# Thermistor_ADC.net
KiCad netlist of a schematic drawn in Altium Designer
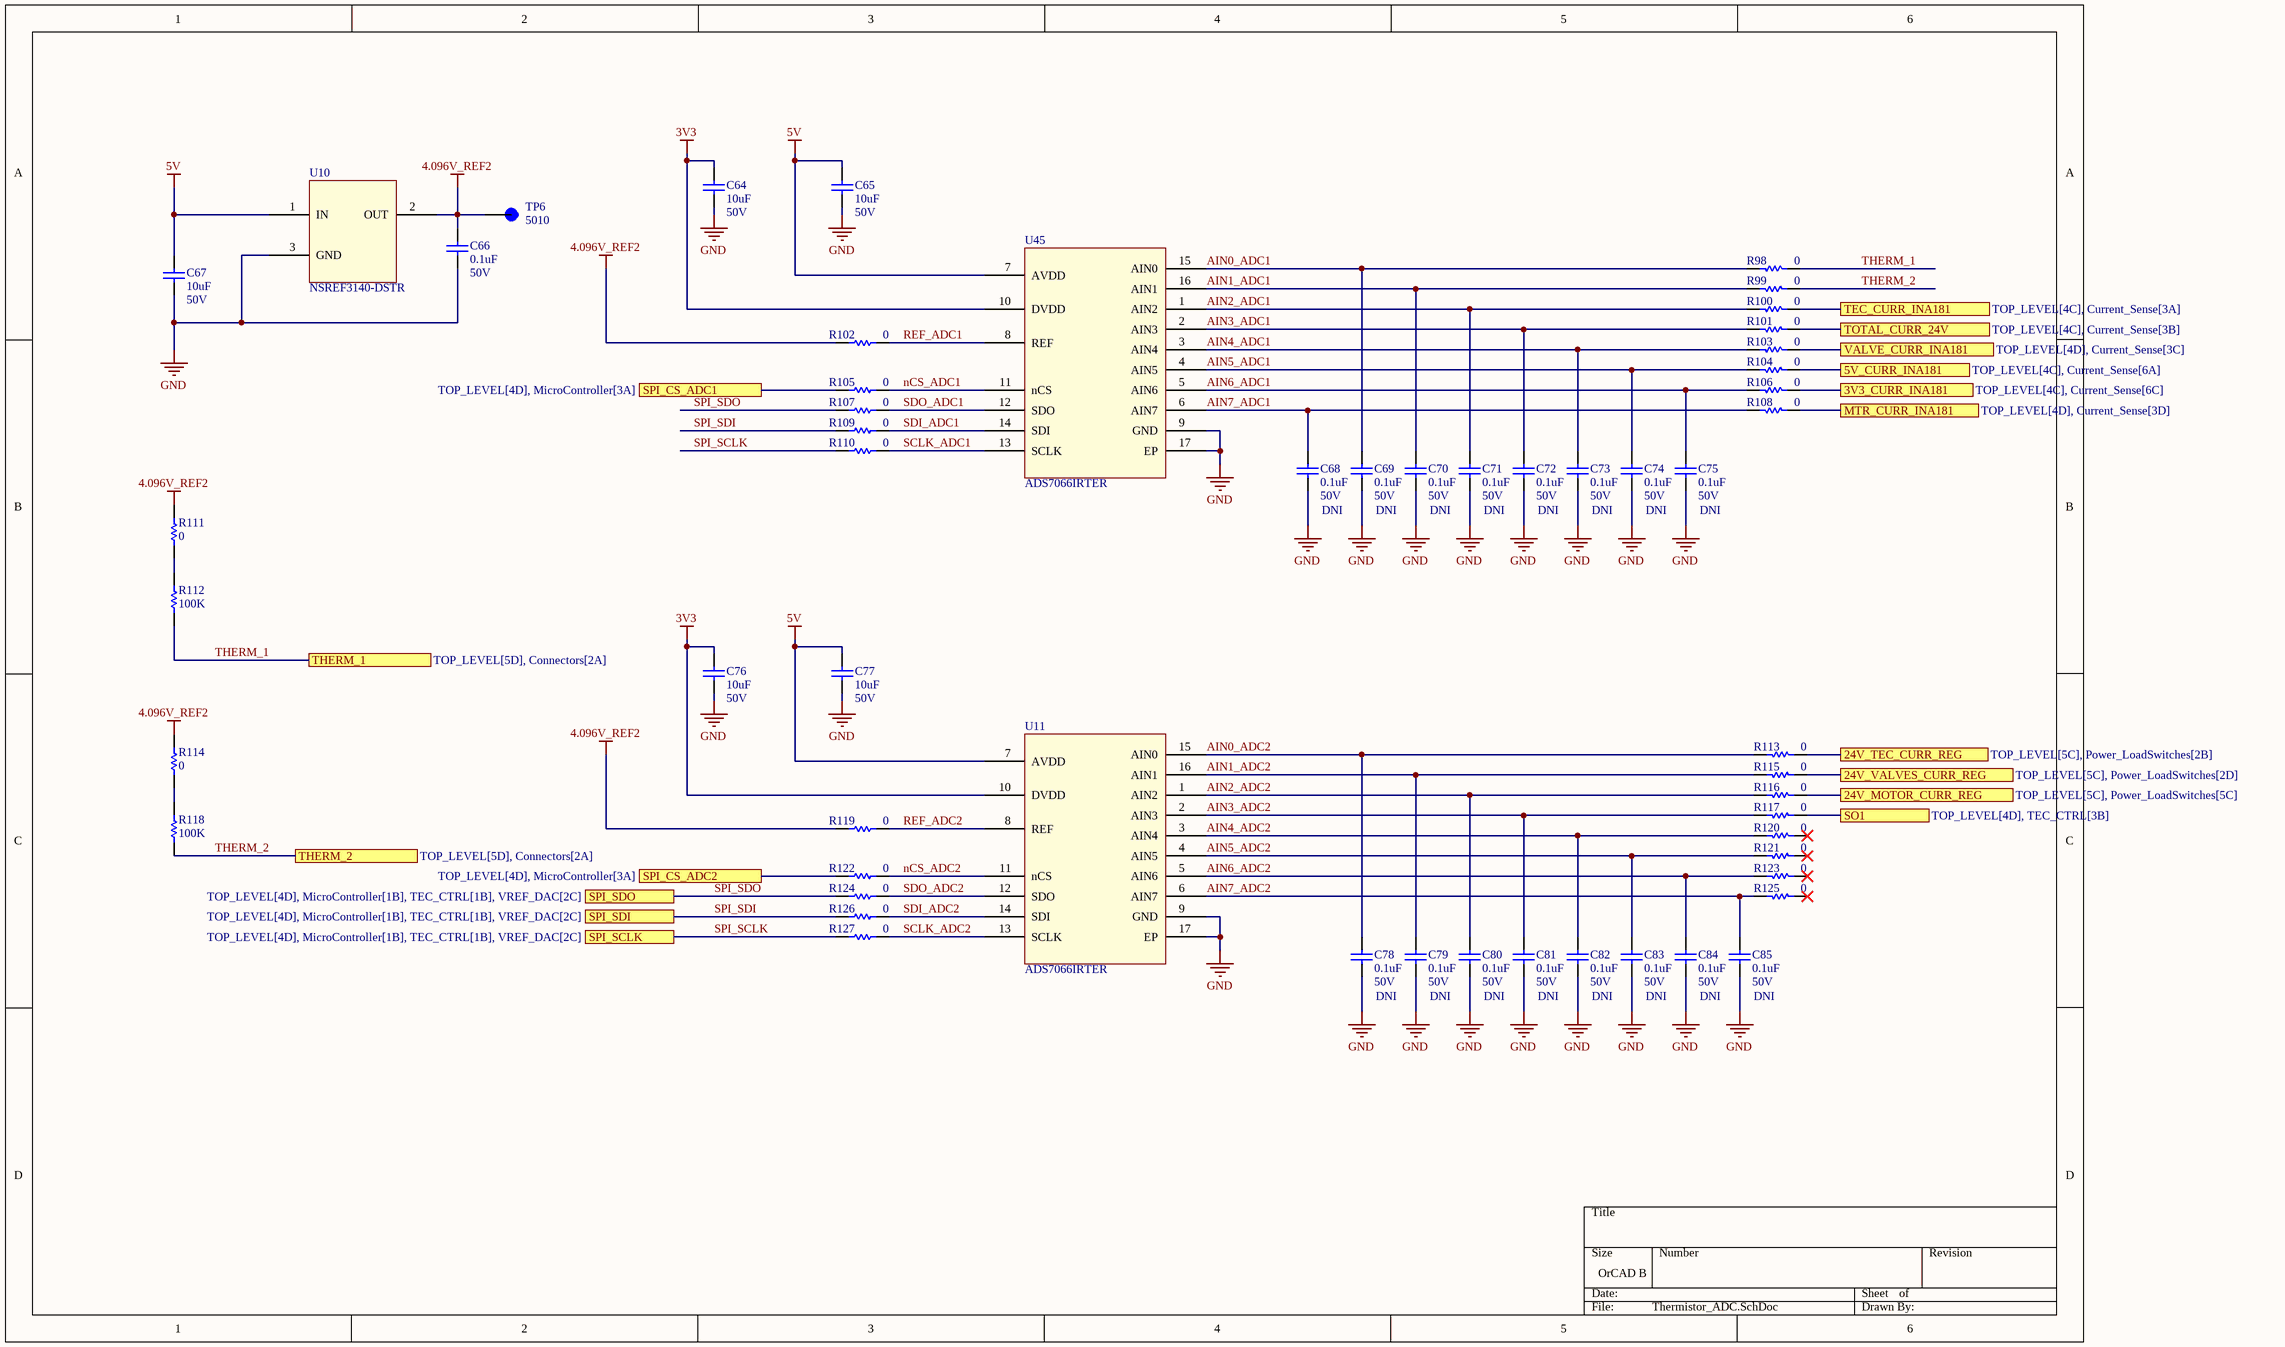
[diagram p0: Thermistor_ADC.SchDoc]

(export (version "E")
  (design (tool "Eeschema 10.0.6"))
  (components
    (comp (ref "C64")
      (value "10uF")
      (footprint "DEFAULT_CAPACITOR_0805")
      (description "CAP CER 10UF 50V X5R 0805")
      (fields (field (name "RATING") "50V") (field (name "Comment") "GRM21BR61H106KE43L"))
      (libsource (lib "Avery Altium Llibrary") (part "GRM21BR61H106KE43L"))
    )
    (comp (ref "C65")
      (value "10uF")
      (footprint "DEFAULT_CAPACITOR_0805")
      (description "CAP CER 10UF 50V X5R 0805")
      (fields (field (name "RATING") "50V") (field (name "Comment") "GRM21BR61H106KE43L"))
      (libsource (lib "Avery Altium Llibrary") (part "GRM21BR61H106KE43L"))
    )
    (comp (ref "C66")
      (value "0.1uF")
      (footprint "DEFAULT_CAPACITOR_0805")
      (description "CAP CER 0.1UF 50V X7R 0805")
      (fields
        (field (name "MANUFACTURER") "Cal-Chip Electronics, Inc.")
        (field (name "RATING") "50V")
        (field (name "Comment") "KGM21NR71H104KT")
      )
      (libsource (lib "Avery Altium Llibrary") (part "KGM21NR71H104KT"))
    )
    (comp (ref "C67")
      (value "10uF")
      (footprint "DEFAULT_CAPACITOR_0805")
      (description "CAP CER 10UF 50V X5R 0805")
      (fields (field (name "RATING") "50V") (field (name "Comment") "GRM21BR61H106KE43L"))
      (libsource (lib "Avery Altium Llibrary") (part "GRM21BR61H106KE43L"))
    )
    (comp (ref "C68")
      (value "DNI")
      (footprint "DEFAULT_CAPACITOR_0805")
      (description "CAP CER 0.1UF 50V X7R 0805")
      (fields
        (field (name "MANUFACTURER") "Cal-Chip Electronics, Inc.")
        (field (name "RATING") "50V")
        (field (name "ALTIUM_VALUE") "0.1uF")
      )
      (libsource (lib "Avery Altium Llibrary") (part "KGM21NR71H104KT"))
    )
    (comp (ref "C69")
      (value "DNI")
      (footprint "DEFAULT_CAPACITOR_0805")
      (description "CAP CER 0.1UF 50V X7R 0805")
      (fields
        (field (name "MANUFACTURER") "Cal-Chip Electronics, Inc.")
        (field (name "RATING") "50V")
        (field (name "ALTIUM_VALUE") "0.1uF")
      )
      (libsource (lib "Avery Altium Llibrary") (part "KGM21NR71H104KT"))
    )
    (comp (ref "C70")
      (value "DNI")
      (footprint "DEFAULT_CAPACITOR_0805")
      (description "CAP CER 0.1UF 50V X7R 0805")
      (fields
        (field (name "MANUFACTURER") "Cal-Chip Electronics, Inc.")
        (field (name "RATING") "50V")
        (field (name "ALTIUM_VALUE") "0.1uF")
      )
      (libsource (lib "Avery Altium Llibrary") (part "KGM21NR71H104KT"))
    )
    (comp (ref "C71")
      (value "DNI")
      (footprint "DEFAULT_CAPACITOR_0805")
      (description "CAP CER 0.1UF 50V X7R 0805")
      (fields
        (field (name "MANUFACTURER") "Cal-Chip Electronics, Inc.")
        (field (name "RATING") "50V")
        (field (name "ALTIUM_VALUE") "0.1uF")
      )
      (libsource (lib "Avery Altium Llibrary") (part "KGM21NR71H104KT"))
    )
    (comp (ref "C72")
      (value "DNI")
      (footprint "DEFAULT_CAPACITOR_0805")
      (description "CAP CER 0.1UF 50V X7R 0805")
      (fields
        (field (name "MANUFACTURER") "Cal-Chip Electronics, Inc.")
        (field (name "RATING") "50V")
        (field (name "ALTIUM_VALUE") "0.1uF")
      )
      (libsource (lib "Avery Altium Llibrary") (part "KGM21NR71H104KT"))
    )
    (comp (ref "C73")
      (value "DNI")
      (footprint "DEFAULT_CAPACITOR_0805")
      (description "CAP CER 0.1UF 50V X7R 0805")
      (fields
        (field (name "MANUFACTURER") "Cal-Chip Electronics, Inc.")
        (field (name "RATING") "50V")
        (field (name "ALTIUM_VALUE") "0.1uF")
      )
      (libsource (lib "Avery Altium Llibrary") (part "KGM21NR71H104KT"))
    )
    (comp (ref "C74")
      (value "DNI")
      (footprint "DEFAULT_CAPACITOR_0805")
      (description "CAP CER 0.1UF 50V X7R 0805")
      (fields
        (field (name "MANUFACTURER") "Cal-Chip Electronics, Inc.")
        (field (name "RATING") "50V")
        (field (name "ALTIUM_VALUE") "0.1uF")
      )
      (libsource (lib "Avery Altium Llibrary") (part "KGM21NR71H104KT"))
    )
    (comp (ref "C75")
      (value "DNI")
      (footprint "DEFAULT_CAPACITOR_0805")
      (description "CAP CER 0.1UF 50V X7R 0805")
      (fields
        (field (name "MANUFACTURER") "Cal-Chip Electronics, Inc.")
        (field (name "RATING") "50V")
        (field (name "ALTIUM_VALUE") "0.1uF")
      )
      (libsource (lib "Avery Altium Llibrary") (part "KGM21NR71H104KT"))
    )
    (comp (ref "C76")
      (value "10uF")
      (footprint "DEFAULT_CAPACITOR_0805")
      (description "CAP CER 10UF 50V X5R 0805")
      (fields (field (name "RATING") "50V") (field (name "Comment") "GRM21BR61H106KE43L"))
      (libsource (lib "Avery Altium Llibrary") (part "GRM21BR61H106KE43L"))
    )
    (comp (ref "C77")
      (value "10uF")
      (footprint "DEFAULT_CAPACITOR_0805")
      (description "CAP CER 10UF 50V X5R 0805")
      (fields (field (name "RATING") "50V") (field (name "Comment") "GRM21BR61H106KE43L"))
      (libsource (lib "Avery Altium Llibrary") (part "GRM21BR61H106KE43L"))
    )
    (comp (ref "C78")
      (value "DNI")
      (footprint "DEFAULT_CAPACITOR_0805")
      (description "CAP CER 0.1UF 50V X7R 0805")
      (fields
        (field (name "MANUFACTURER") "Cal-Chip Electronics, Inc.")
        (field (name "RATING") "50V")
        (field (name "ALTIUM_VALUE") "0.1uF")
      )
      (libsource (lib "Avery Altium Llibrary") (part "KGM21NR71H104KT"))
    )
    (comp (ref "C79")
      (value "DNI")
      (footprint "DEFAULT_CAPACITOR_0805")
      (description "CAP CER 0.1UF 50V X7R 0805")
      (fields
        (field (name "MANUFACTURER") "Cal-Chip Electronics, Inc.")
        (field (name "RATING") "50V")
        (field (name "ALTIUM_VALUE") "0.1uF")
      )
      (libsource (lib "Avery Altium Llibrary") (part "KGM21NR71H104KT"))
    )
    (comp (ref "C80")
      (value "DNI")
      (footprint "DEFAULT_CAPACITOR_0805")
      (description "CAP CER 0.1UF 50V X7R 0805")
      (fields
        (field (name "MANUFACTURER") "Cal-Chip Electronics, Inc.")
        (field (name "RATING") "50V")
        (field (name "ALTIUM_VALUE") "0.1uF")
      )
      (libsource (lib "Avery Altium Llibrary") (part "KGM21NR71H104KT"))
    )
    (comp (ref "C81")
      (value "DNI")
      (footprint "DEFAULT_CAPACITOR_0805")
      (description "CAP CER 0.1UF 50V X7R 0805")
      (fields
        (field (name "MANUFACTURER") "Cal-Chip Electronics, Inc.")
        (field (name "RATING") "50V")
        (field (name "ALTIUM_VALUE") "0.1uF")
      )
      (libsource (lib "Avery Altium Llibrary") (part "KGM21NR71H104KT"))
    )
    (comp (ref "C82")
      (value "DNI")
      (footprint "DEFAULT_CAPACITOR_0805")
      (description "CAP CER 0.1UF 50V X7R 0805")
      (fields
        (field (name "MANUFACTURER") "Cal-Chip Electronics, Inc.")
        (field (name "RATING") "50V")
        (field (name "ALTIUM_VALUE") "0.1uF")
      )
      (libsource (lib "Avery Altium Llibrary") (part "KGM21NR71H104KT"))
    )
    (comp (ref "C83")
      (value "DNI")
      (footprint "DEFAULT_CAPACITOR_0805")
      (description "CAP CER 0.1UF 50V X7R 0805")
      (fields
        (field (name "MANUFACTURER") "Cal-Chip Electronics, Inc.")
        (field (name "RATING") "50V")
        (field (name "ALTIUM_VALUE") "0.1uF")
      )
      (libsource (lib "Avery Altium Llibrary") (part "KGM21NR71H104KT"))
    )
    (comp (ref "C84")
      (value "DNI")
      (footprint "DEFAULT_CAPACITOR_0805")
      (description "CAP CER 0.1UF 50V X7R 0805")
      (fields
        (field (name "MANUFACTURER") "Cal-Chip Electronics, Inc.")
        (field (name "RATING") "50V")
        (field (name "ALTIUM_VALUE") "0.1uF")
      )
      (libsource (lib "Avery Altium Llibrary") (part "KGM21NR71H104KT"))
    )
    (comp (ref "C85")
      (value "DNI")
      (footprint "DEFAULT_CAPACITOR_0805")
      (description "CAP CER 0.1UF 50V X7R 0805")
      (fields
        (field (name "MANUFACTURER") "Cal-Chip Electronics, Inc.")
        (field (name "RATING") "50V")
        (field (name "ALTIUM_VALUE") "0.1uF")
      )
      (libsource (lib "Avery Altium Llibrary") (part "KGM21NR71H104KT"))
    )
    (comp (ref "R98")
      (value "0")
      (footprint "DEFAULT_RESISTOR_0805")
      (description "RES 0 OHM JUMPER 1/8W 0805")
      (fields (field (name "POWER") "1/8W") (field (name "Comment") "RC0805JR-070RL"))
      (libsource (lib "Avery Altium Llibrary") (part "RC0805JR-070RL"))
    )
    (comp (ref "R99")
      (value "0")
      (footprint "DEFAULT_RESISTOR_0805")
      (description "RES 0 OHM JUMPER 1/8W 0805")
      (fields (field (name "POWER") "1/8W") (field (name "Comment") "RC0805JR-070RL"))
      (libsource (lib "Avery Altium Llibrary") (part "RC0805JR-070RL"))
    )
    (comp (ref "R100")
      (value "0")
      (footprint "DEFAULT_RESISTOR_0805")
      (description "RES 0 OHM JUMPER 1/8W 0805")
      (fields (field (name "POWER") "1/8W") (field (name "Comment") "RC0805JR-070RL"))
      (libsource (lib "Avery Altium Llibrary") (part "RC0805JR-070RL"))
    )
    (comp (ref "R101")
      (value "0")
      (footprint "DEFAULT_RESISTOR_0805")
      (description "RES 0 OHM JUMPER 1/8W 0805")
      (fields (field (name "POWER") "1/8W") (field (name "Comment") "RC0805JR-070RL"))
      (libsource (lib "Avery Altium Llibrary") (part "RC0805JR-070RL"))
    )
    (comp (ref "R102")
      (value "0")
      (footprint "DEFAULT_RESISTOR_0805")
      (description "RES 0 OHM JUMPER 1/8W 0805")
      (fields (field (name "POWER") "1/8W") (field (name "Comment") "RC0805JR-070RL"))
      (libsource (lib "Avery Altium Llibrary") (part "RC0805JR-070RL"))
    )
    (comp (ref "R103")
      (value "0")
      (footprint "DEFAULT_RESISTOR_0805")
      (description "RES 0 OHM JUMPER 1/8W 0805")
      (fields (field (name "POWER") "1/8W") (field (name "Comment") "RC0805JR-070RL"))
      (libsource (lib "Avery Altium Llibrary") (part "RC0805JR-070RL"))
    )
    (comp (ref "R104")
      (value "0")
      (footprint "DEFAULT_RESISTOR_0805")
      (description "RES 0 OHM JUMPER 1/8W 0805")
      (fields (field (name "POWER") "1/8W") (field (name "Comment") "RC0805JR-070RL"))
      (libsource (lib "Avery Altium Llibrary") (part "RC0805JR-070RL"))
    )
    (comp (ref "R105")
      (value "0")
      (footprint "DEFAULT_RESISTOR_0805")
      (description "RES 0 OHM JUMPER 1/8W 0805")
      (fields (field (name "POWER") "1/8W") (field (name "Comment") "RC0805JR-070RL"))
      (libsource (lib "Avery Altium Llibrary") (part "RC0805JR-070RL"))
    )
    (comp (ref "R106")
      (value "0")
      (footprint "DEFAULT_RESISTOR_0805")
      (description "RES 0 OHM JUMPER 1/8W 0805")
      (fields (field (name "POWER") "1/8W") (field (name "Comment") "RC0805JR-070RL"))
      (libsource (lib "Avery Altium Llibrary") (part "RC0805JR-070RL"))
    )
    (comp (ref "R107")
      (value "0")
      (footprint "DEFAULT_RESISTOR_0805")
      (description "RES 0 OHM JUMPER 1/8W 0805")
      (fields (field (name "POWER") "1/8W") (field (name "Comment") "RC0805JR-070RL"))
      (libsource (lib "Avery Altium Llibrary") (part "RC0805JR-070RL"))
    )
    (comp (ref "R108")
      (value "0")
      (footprint "DEFAULT_RESISTOR_0805")
      (description "RES 0 OHM JUMPER 1/8W 0805")
      (fields (field (name "POWER") "1/8W") (field (name "Comment") "RC0805JR-070RL"))
      (libsource (lib "Avery Altium Llibrary") (part "RC0805JR-070RL"))
    )
    (comp (ref "R109")
      (value "0")
      (footprint "DEFAULT_RESISTOR_0805")
      (description "RES 0 OHM JUMPER 1/8W 0805")
      (fields (field (name "POWER") "1/8W") (field (name "Comment") "RC0805JR-070RL"))
      (libsource (lib "Avery Altium Llibrary") (part "RC0805JR-070RL"))
    )
    (comp (ref "R110")
      (value "0")
      (footprint "DEFAULT_RESISTOR_0805")
      (description "RES 0 OHM JUMPER 1/8W 0805")
      (fields (field (name "POWER") "1/8W") (field (name "Comment") "RC0805JR-070RL"))
      (libsource (lib "Avery Altium Llibrary") (part "RC0805JR-070RL"))
    )
    (comp (ref "R111")
      (value "0")
      (footprint "DEFAULT_RESISTOR_0805")
      (description "RES 0 OHM JUMPER 1/8W 0805")
      (fields (field (name "POWER") "1/8W") (field (name "Comment") "RC0805JR-070RL"))
      (libsource (lib "Avery Altium Llibrary") (part "RC0805JR-070RL"))
    )
    (comp (ref "R112")
      (value "100K")
      (footprint "DEFAULT_RESISTOR_0805")
      (description "RES SMD 100K OHM 0.1% 1/8W 0805")
      (fields (field (name "POWER") "1/8W") (field (name "TOLERANCE") "0.1%"))
      (libsource (lib "Avery Altium Llibrary") (part "RG2012P-104-B-T5"))
    )
    (comp (ref "R113")
      (value "0")
      (footprint "DEFAULT_RESISTOR_0805")
      (description "RES 0 OHM JUMPER 1/8W 0805")
      (fields (field (name "POWER") "1/8W") (field (name "Comment") "RC0805JR-070RL"))
      (libsource (lib "Avery Altium Llibrary") (part "RC0805JR-070RL"))
    )
    (comp (ref "R114")
      (value "0")
      (footprint "DEFAULT_RESISTOR_0805")
      (description "RES 0 OHM JUMPER 1/8W 0805")
      (fields (field (name "POWER") "1/8W") (field (name "Comment") "RC0805JR-070RL"))
      (libsource (lib "Avery Altium Llibrary") (part "RC0805JR-070RL"))
    )
    (comp (ref "R115")
      (value "0")
      (footprint "DEFAULT_RESISTOR_0805")
      (description "RES 0 OHM JUMPER 1/8W 0805")
      (fields (field (name "POWER") "1/8W") (field (name "Comment") "RC0805JR-070RL"))
      (libsource (lib "Avery Altium Llibrary") (part "RC0805JR-070RL"))
    )
    (comp (ref "R116")
      (value "0")
      (footprint "DEFAULT_RESISTOR_0805")
      (description "RES 0 OHM JUMPER 1/8W 0805")
      (fields (field (name "POWER") "1/8W") (field (name "Comment") "RC0805JR-070RL"))
      (libsource (lib "Avery Altium Llibrary") (part "RC0805JR-070RL"))
    )
    (comp (ref "R117")
      (value "0")
      (footprint "DEFAULT_RESISTOR_0805")
      (description "RES 0 OHM JUMPER 1/8W 0805")
      (fields (field (name "POWER") "1/8W") (field (name "Comment") "RC0805JR-070RL"))
      (libsource (lib "Avery Altium Llibrary") (part "RC0805JR-070RL"))
    )
    (comp (ref "R118")
      (value "100K")
      (footprint "DEFAULT_RESISTOR_0805")
      (description "RES SMD 100K OHM 0.1% 1/8W 0805")
      (fields (field (name "POWER") "1/8W") (field (name "TOLERANCE") "0.1%"))
      (libsource (lib "Avery Altium Llibrary") (part "RG2012P-104-B-T5"))
    )
    (comp (ref "R119")
      (value "0")
      (footprint "DEFAULT_RESISTOR_0805")
      (description "RES 0 OHM JUMPER 1/8W 0805")
      (fields (field (name "POWER") "1/8W") (field (name "Comment") "RC0805JR-070RL"))
      (libsource (lib "Avery Altium Llibrary") (part "RC0805JR-070RL"))
    )
    (comp (ref "R120")
      (value "0")
      (footprint "DEFAULT_RESISTOR_0805")
      (description "RES 0 OHM JUMPER 1/8W 0805")
      (fields (field (name "POWER") "1/8W") (field (name "Comment") "RC0805JR-070RL"))
      (libsource (lib "Avery Altium Llibrary") (part "RC0805JR-070RL"))
    )
    (comp (ref "R121")
      (value "0")
      (footprint "DEFAULT_RESISTOR_0805")
      (description "RES 0 OHM JUMPER 1/8W 0805")
      (fields (field (name "POWER") "1/8W") (field (name "Comment") "RC0805JR-070RL"))
      (libsource (lib "Avery Altium Llibrary") (part "RC0805JR-070RL"))
    )
    (comp (ref "R122")
      (value "0")
      (footprint "DEFAULT_RESISTOR_0805")
      (description "RES 0 OHM JUMPER 1/8W 0805")
      (fields (field (name "POWER") "1/8W") (field (name "Comment") "RC0805JR-070RL"))
      (libsource (lib "Avery Altium Llibrary") (part "RC0805JR-070RL"))
    )
    (comp (ref "R123")
      (value "0")
      (footprint "DEFAULT_RESISTOR_0805")
      (description "RES 0 OHM JUMPER 1/8W 0805")
      (fields (field (name "POWER") "1/8W") (field (name "Comment") "RC0805JR-070RL"))
      (libsource (lib "Avery Altium Llibrary") (part "RC0805JR-070RL"))
    )
    (comp (ref "R124")
      (value "0")
      (footprint "DEFAULT_RESISTOR_0805")
      (description "RES 0 OHM JUMPER 1/8W 0805")
      (fields (field (name "POWER") "1/8W") (field (name "Comment") "RC0805JR-070RL"))
      (libsource (lib "Avery Altium Llibrary") (part "RC0805JR-070RL"))
    )
    (comp (ref "R125")
      (value "0")
      (footprint "DEFAULT_RESISTOR_0805")
      (description "RES 0 OHM JUMPER 1/8W 0805")
      (fields (field (name "POWER") "1/8W") (field (name "Comment") "RC0805JR-070RL"))
      (libsource (lib "Avery Altium Llibrary") (part "RC0805JR-070RL"))
    )
    (comp (ref "R126")
      (value "0")
      (footprint "DEFAULT_RESISTOR_0805")
      (description "RES 0 OHM JUMPER 1/8W 0805")
      (fields (field (name "POWER") "1/8W") (field (name "Comment") "RC0805JR-070RL"))
      (libsource (lib "Avery Altium Llibrary") (part "RC0805JR-070RL"))
    )
    (comp (ref "R127")
      (value "0")
      (footprint "DEFAULT_RESISTOR_0805")
      (description "RES 0 OHM JUMPER 1/8W 0805")
      (fields (field (name "POWER") "1/8W") (field (name "Comment") "RC0805JR-070RL"))
      (libsource (lib "Avery Altium Llibrary") (part "RC0805JR-070RL"))
    )
    (comp (ref "TP6")
      (value "5010")
      (footprint "TP_5011")
      (description "PC TEST POINT MULTIPURPOSE RED")
      (libsource (lib "Avery Altium Llibrary") (part "5010"))
    )
    (comp (ref "U10")
      (value "NSREF3140-DSTR")
      (footprint "NSREF3140DSTR-SOT23-3L")
      (description "0.2% ACCURACY 15PPM 4V REF")
      (fields (field (name "MANUFACTURER") "NOVOSENSE"))
      (libsource (lib "Avery Altium Llibrary") (part "NSREF3140-DSTR"))
    )
    (comp (ref "U11")
      (value "ADS7066IRTER")
      (footprint "ADS7066IRTER-WQFN16")
      (description "16 Bit Analog to Digital Converter 8 Input 1 SAR 16-WQFN (3x3)")
      (fields (field (name "MANUFACTURER") "Texas Instruments"))
      (libsource (lib "Avery Schem Library") (part "ADS7066IRTER"))
    )
    (comp (ref "U45")
      (value "ADS7066IRTER")
      (footprint "ADS7066IRTER-WQFN16")
      (description "16 Bit Analog to Digital Converter 8 Input 1 SAR 16-WQFN (3x3)")
      (fields (field (name "MANUFACTURER") "Texas Instruments"))
      (libsource (lib "Avery Schem Library") (part "ADS7066IRTER"))
    )
  )
  (nets
    (net (code "1") (name "/3V3_CURR_INA181") (class "Default")
      (node (ref "R106") (pin "2") (pinfunction "2_2") (pintype "passive"))
    )
    (net (code "2") (name "/5V_CURR_INA181") (class "Default")
      (node (ref "R104") (pin "2") (pinfunction "2_2") (pintype "passive"))
    )
    (net (code "3") (name "/24V_MOTOR_CURR_REG") (class "Default")
      (node (ref "R116") (pin "2") (pinfunction "2_2") (pintype "passive"))
    )
    (net (code "4") (name "/24V_TEC_CURR_REG") (class "Default")
      (node (ref "R113") (pin "2") (pinfunction "2_2") (pintype "passive"))
    )
    (net (code "5") (name "/24V_VALVES_CURR_REG") (class "Default")
      (node (ref "R115") (pin "2") (pinfunction "2_2") (pintype "passive"))
    )
    (net (code "6") (name "/AIN0_ADC1") (class "Default")
      (node (ref "C69") (pin "2") (pinfunction "2_2") (pintype "passive"))
      (node (ref "R98") (pin "1") (pinfunction "1_1") (pintype "passive"))
      (node (ref "U45") (pin "15") (pinfunction "AIN0_15") (pintype "passive"))
    )
    (net (code "7") (name "/AIN0_ADC2") (class "Default")
      (node (ref "C78") (pin "2") (pinfunction "2_2") (pintype "passive"))
      (node (ref "R113") (pin "1") (pinfunction "1_1") (pintype "passive"))
      (node (ref "U11") (pin "15") (pinfunction "AIN0_15") (pintype "passive"))
    )
    (net (code "8") (name "/AIN1_ADC1") (class "Default")
      (node (ref "C70") (pin "2") (pinfunction "2_2") (pintype "passive"))
      (node (ref "R99") (pin "1") (pinfunction "1_1") (pintype "passive"))
      (node (ref "U45") (pin "16") (pinfunction "AIN1_16") (pintype "passive"))
    )
    (net (code "9") (name "/AIN1_ADC2") (class "Default")
      (node (ref "C79") (pin "2") (pinfunction "2_2") (pintype "passive"))
      (node (ref "R115") (pin "1") (pinfunction "1_1") (pintype "passive"))
      (node (ref "U11") (pin "16") (pinfunction "AIN1_16") (pintype "passive"))
    )
    (net (code "10") (name "/AIN2_ADC1") (class "Default")
      (node (ref "C71") (pin "2") (pinfunction "2_2") (pintype "passive"))
      (node (ref "R100") (pin "1") (pinfunction "1_1") (pintype "passive"))
      (node (ref "U45") (pin "1") (pinfunction "AIN2_1") (pintype "passive"))
    )
    (net (code "11") (name "/AIN2_ADC2") (class "Default")
      (node (ref "C80") (pin "2") (pinfunction "2_2") (pintype "passive"))
      (node (ref "R116") (pin "1") (pinfunction "1_1") (pintype "passive"))
      (node (ref "U11") (pin "1") (pinfunction "AIN2_1") (pintype "passive"))
    )
    (net (code "12") (name "/AIN3_ADC1") (class "Default")
      (node (ref "C72") (pin "2") (pinfunction "2_2") (pintype "passive"))
      (node (ref "R101") (pin "1") (pinfunction "1_1") (pintype "passive"))
      (node (ref "U45") (pin "2") (pinfunction "AIN3_2") (pintype "passive"))
    )
    (net (code "13") (name "/AIN3_ADC2") (class "Default")
      (node (ref "C81") (pin "2") (pinfunction "2_2") (pintype "passive"))
      (node (ref "R117") (pin "1") (pinfunction "1_1") (pintype "passive"))
      (node (ref "U11") (pin "2") (pinfunction "AIN3_2") (pintype "passive"))
    )
    (net (code "14") (name "/AIN4_ADC1") (class "Default")
      (node (ref "C73") (pin "2") (pinfunction "2_2") (pintype "passive"))
      (node (ref "R103") (pin "1") (pinfunction "1_1") (pintype "passive"))
      (node (ref "U45") (pin "3") (pinfunction "AIN4_3") (pintype "passive"))
    )
    (net (code "15") (name "/AIN4_ADC2") (class "Default")
      (node (ref "C82") (pin "2") (pinfunction "2_2") (pintype "passive"))
      (node (ref "R120") (pin "1") (pinfunction "1_1") (pintype "passive"))
      (node (ref "U11") (pin "3") (pinfunction "AIN4_3") (pintype "passive"))
    )
    (net (code "16") (name "/AIN5_ADC1") (class "Default")
      (node (ref "C74") (pin "2") (pinfunction "2_2") (pintype "passive"))
      (node (ref "R104") (pin "1") (pinfunction "1_1") (pintype "passive"))
      (node (ref "U45") (pin "4") (pinfunction "AIN5_4") (pintype "passive"))
    )
    (net (code "17") (name "/AIN5_ADC2") (class "Default")
      (node (ref "C83") (pin "2") (pinfunction "2_2") (pintype "passive"))
      (node (ref "R121") (pin "1") (pinfunction "1_1") (pintype "passive"))
      (node (ref "U11") (pin "4") (pinfunction "AIN5_4") (pintype "passive"))
    )
    (net (code "18") (name "/AIN6_ADC1") (class "Default")
      (node (ref "C75") (pin "2") (pinfunction "2_2") (pintype "passive"))
      (node (ref "R106") (pin "1") (pinfunction "1_1") (pintype "passive"))
      (node (ref "U45") (pin "5") (pinfunction "AIN6_5") (pintype "passive"))
    )
    (net (code "19") (name "/AIN6_ADC2") (class "Default")
      (node (ref "C84") (pin "2") (pinfunction "2_2") (pintype "passive"))
      (node (ref "R123") (pin "1") (pinfunction "1_1") (pintype "passive"))
      (node (ref "U11") (pin "5") (pinfunction "AIN6_5") (pintype "passive"))
    )
    (net (code "20") (name "/AIN7_ADC1") (class "Default")
      (node (ref "C68") (pin "2") (pinfunction "2_2") (pintype "passive"))
      (node (ref "R108") (pin "1") (pinfunction "1_1") (pintype "passive"))
      (node (ref "U45") (pin "6") (pinfunction "AIN7_6") (pintype "passive"))
    )
    (net (code "21") (name "/AIN7_ADC2") (class "Default")
      (node (ref "C85") (pin "2") (pinfunction "2_2") (pintype "passive"))
      (node (ref "R125") (pin "1") (pinfunction "1_1") (pintype "passive"))
      (node (ref "U11") (pin "6") (pinfunction "AIN7_6") (pintype "passive"))
    )
    (net (code "22") (name "/MTR_CURR_INA181") (class "Default")
      (node (ref "R108") (pin "2") (pinfunction "2_2") (pintype "passive"))
    )
    (net (code "23") (name "/REF_ADC1") (class "Default")
      (node (ref "R102") (pin "1") (pinfunction "1_1") (pintype "passive"))
      (node (ref "U45") (pin "8") (pinfunction "REF_8") (pintype "passive"))
    )
    (net (code "24") (name "/REF_ADC2") (class "Default")
      (node (ref "R119") (pin "1") (pinfunction "1_1") (pintype "passive"))
      (node (ref "U11") (pin "8") (pinfunction "REF_8") (pintype "passive"))
    )
    (net (code "25") (name "/SCLK_ADC1") (class "Default")
      (node (ref "R110") (pin "1") (pinfunction "1_1") (pintype "passive"))
      (node (ref "U45") (pin "13") (pinfunction "SCLK_13") (pintype "passive"))
    )
    (net (code "26") (name "/SCLK_ADC2") (class "Default")
      (node (ref "R127") (pin "1") (pinfunction "1_1") (pintype "passive"))
      (node (ref "U11") (pin "13") (pinfunction "SCLK_13") (pintype "passive"))
    )
    (net (code "27") (name "/SDI_ADC1") (class "Default")
      (node (ref "R109") (pin "1") (pinfunction "1_1") (pintype "passive"))
      (node (ref "U45") (pin "14") (pinfunction "SDI_14") (pintype "passive"))
    )
    (net (code "28") (name "/SDI_ADC2") (class "Default")
      (node (ref "R126") (pin "1") (pinfunction "1_1") (pintype "passive"))
      (node (ref "U11") (pin "14") (pinfunction "SDI_14") (pintype "passive"))
    )
    (net (code "29") (name "/SDO_ADC1") (class "Default")
      (node (ref "R107") (pin "1") (pinfunction "1_1") (pintype "passive"))
      (node (ref "U45") (pin "12") (pinfunction "SDO_12") (pintype "passive"))
    )
    (net (code "30") (name "/SDO_ADC2") (class "Default")
      (node (ref "R124") (pin "1") (pinfunction "1_1") (pintype "passive"))
      (node (ref "U11") (pin "12") (pinfunction "SDO_12") (pintype "passive"))
    )
    (net (code "31") (name "/SO1") (class "Default")
      (node (ref "R117") (pin "2") (pinfunction "2_2") (pintype "passive"))
    )
    (net (code "32") (name "/SPI_CS_ADC1") (class "Default")
      (node (ref "R105") (pin "2") (pinfunction "2_2") (pintype "passive"))
    )
    (net (code "33") (name "/SPI_CS_ADC2") (class "Default")
      (node (ref "R122") (pin "2") (pinfunction "2_2") (pintype "passive"))
    )
    (net (code "34") (name "/SPI_SCLK") (class "Default")
      (node (ref "R110") (pin "2") (pinfunction "2_2") (pintype "passive"))
      (node (ref "R127") (pin "2") (pinfunction "2_2") (pintype "passive"))
    )
    (net (code "35") (name "/SPI_SDI") (class "Default")
      (node (ref "R109") (pin "2") (pinfunction "2_2") (pintype "passive"))
      (node (ref "R126") (pin "2") (pinfunction "2_2") (pintype "passive"))
    )
    (net (code "36") (name "/SPI_SDO") (class "Default")
      (node (ref "R107") (pin "2") (pinfunction "2_2") (pintype "passive"))
      (node (ref "R124") (pin "2") (pinfunction "2_2") (pintype "passive"))
    )
    (net (code "37") (name "/TEC_CURR_INA181") (class "Default")
      (node (ref "R100") (pin "2") (pinfunction "2_2") (pintype "passive"))
    )
    (net (code "38") (name "/THERM_1") (class "Default")
      (node (ref "R112") (pin "2") (pinfunction "2_2") (pintype "passive"))
      (node (ref "R98") (pin "2") (pinfunction "2_2") (pintype "passive"))
    )
    (net (code "39") (name "/THERM_2") (class "Default")
      (node (ref "R118") (pin "2") (pinfunction "2_2") (pintype "passive"))
      (node (ref "R99") (pin "2") (pinfunction "2_2") (pintype "passive"))
    )
    (net (code "40") (name "/TOTAL_CURR_24V") (class "Default")
      (node (ref "R101") (pin "2") (pinfunction "2_2") (pintype "passive"))
    )
    (net (code "41") (name "/VALVE_CURR_INA181") (class "Default")
      (node (ref "R103") (pin "2") (pinfunction "2_2") (pintype "passive"))
    )
    (net (code "42") (name "/nCS_ADC1") (class "Default")
      (node (ref "R105") (pin "1") (pinfunction "1_1") (pintype "passive"))
      (node (ref "U45") (pin "11") (pinfunction "nCS_11") (pintype "passive"))
    )
    (net (code "43") (name "/nCS_ADC2") (class "Default")
      (node (ref "R122") (pin "1") (pinfunction "1_1") (pintype "passive"))
      (node (ref "U11") (pin "11") (pinfunction "nCS_11") (pintype "passive"))
    )
    (net (code "44") (name "3V3") (class "Default")
      (node (ref "C64") (pin "2") (pinfunction "2_2") (pintype "passive"))
      (node (ref "C76") (pin "2") (pinfunction "2_2") (pintype "passive"))
      (node (ref "U11") (pin "10") (pinfunction "DVDD_10") (pintype "passive"))
      (node (ref "U45") (pin "10") (pinfunction "DVDD_10") (pintype "passive"))
    )
    (net (code "45") (name "4.096V_REF2") (class "Default")
      (node (ref "C66") (pin "2") (pinfunction "2_2") (pintype "passive"))
      (node (ref "R102") (pin "2") (pinfunction "2_2") (pintype "passive"))
      (node (ref "R111") (pin "1") (pinfunction "1_1") (pintype "passive"))
      (node (ref "R114") (pin "1") (pinfunction "1_1") (pintype "passive"))
      (node (ref "R119") (pin "2") (pinfunction "2_2") (pintype "passive"))
      (node (ref "TP6") (pin "TP") (pinfunction "TP_TP") (pintype "passive"))
      (node (ref "U10") (pin "2") (pinfunction "OUT_2") (pintype "passive"))
    )
    (net (code "46") (name "5V") (class "Default")
      (node (ref "C65") (pin "2") (pinfunction "2_2") (pintype "passive"))
      (node (ref "C67") (pin "2") (pinfunction "2_2") (pintype "passive"))
      (node (ref "C77") (pin "2") (pinfunction "2_2") (pintype "passive"))
      (node (ref "U10") (pin "1") (pinfunction "IN_1") (pintype "passive"))
      (node (ref "U11") (pin "7") (pinfunction "AVDD_7") (pintype "passive"))
      (node (ref "U45") (pin "7") (pinfunction "AVDD_7") (pintype "passive"))
    )
    (net (code "47") (name "GND") (class "Default")
      (node (ref "C64") (pin "1") (pinfunction "1_1") (pintype "passive"))
      (node (ref "C65") (pin "1") (pinfunction "1_1") (pintype "passive"))
      (node (ref "C66") (pin "1") (pinfunction "1_1") (pintype "passive"))
      (node (ref "C67") (pin "1") (pinfunction "1_1") (pintype "passive"))
      (node (ref "C68") (pin "1") (pinfunction "1_1") (pintype "passive"))
      (node (ref "C69") (pin "1") (pinfunction "1_1") (pintype "passive"))
      (node (ref "C70") (pin "1") (pinfunction "1_1") (pintype "passive"))
      (node (ref "C71") (pin "1") (pinfunction "1_1") (pintype "passive"))
      (node (ref "C72") (pin "1") (pinfunction "1_1") (pintype "passive"))
      (node (ref "C73") (pin "1") (pinfunction "1_1") (pintype "passive"))
      (node (ref "C74") (pin "1") (pinfunction "1_1") (pintype "passive"))
      (node (ref "C75") (pin "1") (pinfunction "1_1") (pintype "passive"))
      (node (ref "C76") (pin "1") (pinfunction "1_1") (pintype "passive"))
      (node (ref "C77") (pin "1") (pinfunction "1_1") (pintype "passive"))
      (node (ref "C78") (pin "1") (pinfunction "1_1") (pintype "passive"))
      (node (ref "C79") (pin "1") (pinfunction "1_1") (pintype "passive"))
      (node (ref "C80") (pin "1") (pinfunction "1_1") (pintype "passive"))
      (node (ref "C81") (pin "1") (pinfunction "1_1") (pintype "passive"))
      (node (ref "C82") (pin "1") (pinfunction "1_1") (pintype "passive"))
      (node (ref "C83") (pin "1") (pinfunction "1_1") (pintype "passive"))
      (node (ref "C84") (pin "1") (pinfunction "1_1") (pintype "passive"))
      (node (ref "C85") (pin "1") (pinfunction "1_1") (pintype "passive"))
      (node (ref "U10") (pin "3") (pinfunction "GND_3") (pintype "passive"))
      (node (ref "U11") (pin "17") (pinfunction "EP_17") (pintype "passive"))
      (node (ref "U11") (pin "9") (pinfunction "GND_9") (pintype "passive"))
      (node (ref "U45") (pin "17") (pinfunction "EP_17") (pintype "passive"))
      (node (ref "U45") (pin "9") (pinfunction "GND_9") (pintype "passive"))
    )
    (net (code "48") (name "Net-(R111-Pad2)") (class "Default")
      (node (ref "R111") (pin "2") (pinfunction "2_2") (pintype "passive"))
      (node (ref "R112") (pin "1") (pinfunction "1_1") (pintype "passive"))
    )
    (net (code "49") (name "Net-(R114-Pad2)") (class "Default")
      (node (ref "R114") (pin "2") (pinfunction "2_2") (pintype "passive"))
      (node (ref "R118") (pin "1") (pinfunction "1_1") (pintype "passive"))
    )
    (net (code "50") (name "unconnected-(R120-Pad2)") (class "Default")
      (node (ref "R120") (pin "2") (pinfunction "2_2") (pintype "passive+no_connect"))
    )
    (net (code "51") (name "unconnected-(R121-Pad2)") (class "Default")
      (node (ref "R121") (pin "2") (pinfunction "2_2") (pintype "passive+no_connect"))
    )
    (net (code "52") (name "unconnected-(R123-Pad2)") (class "Default")
      (node (ref "R123") (pin "2") (pinfunction "2_2") (pintype "passive+no_connect"))
    )
    (net (code "53") (name "unconnected-(R125-Pad2)") (class "Default")
      (node (ref "R125") (pin "2") (pinfunction "2_2") (pintype "passive+no_connect"))
    )
  )
)
